# A_D_000000_001.net
KiCad netlist of a schematic drawn in Altium Designer
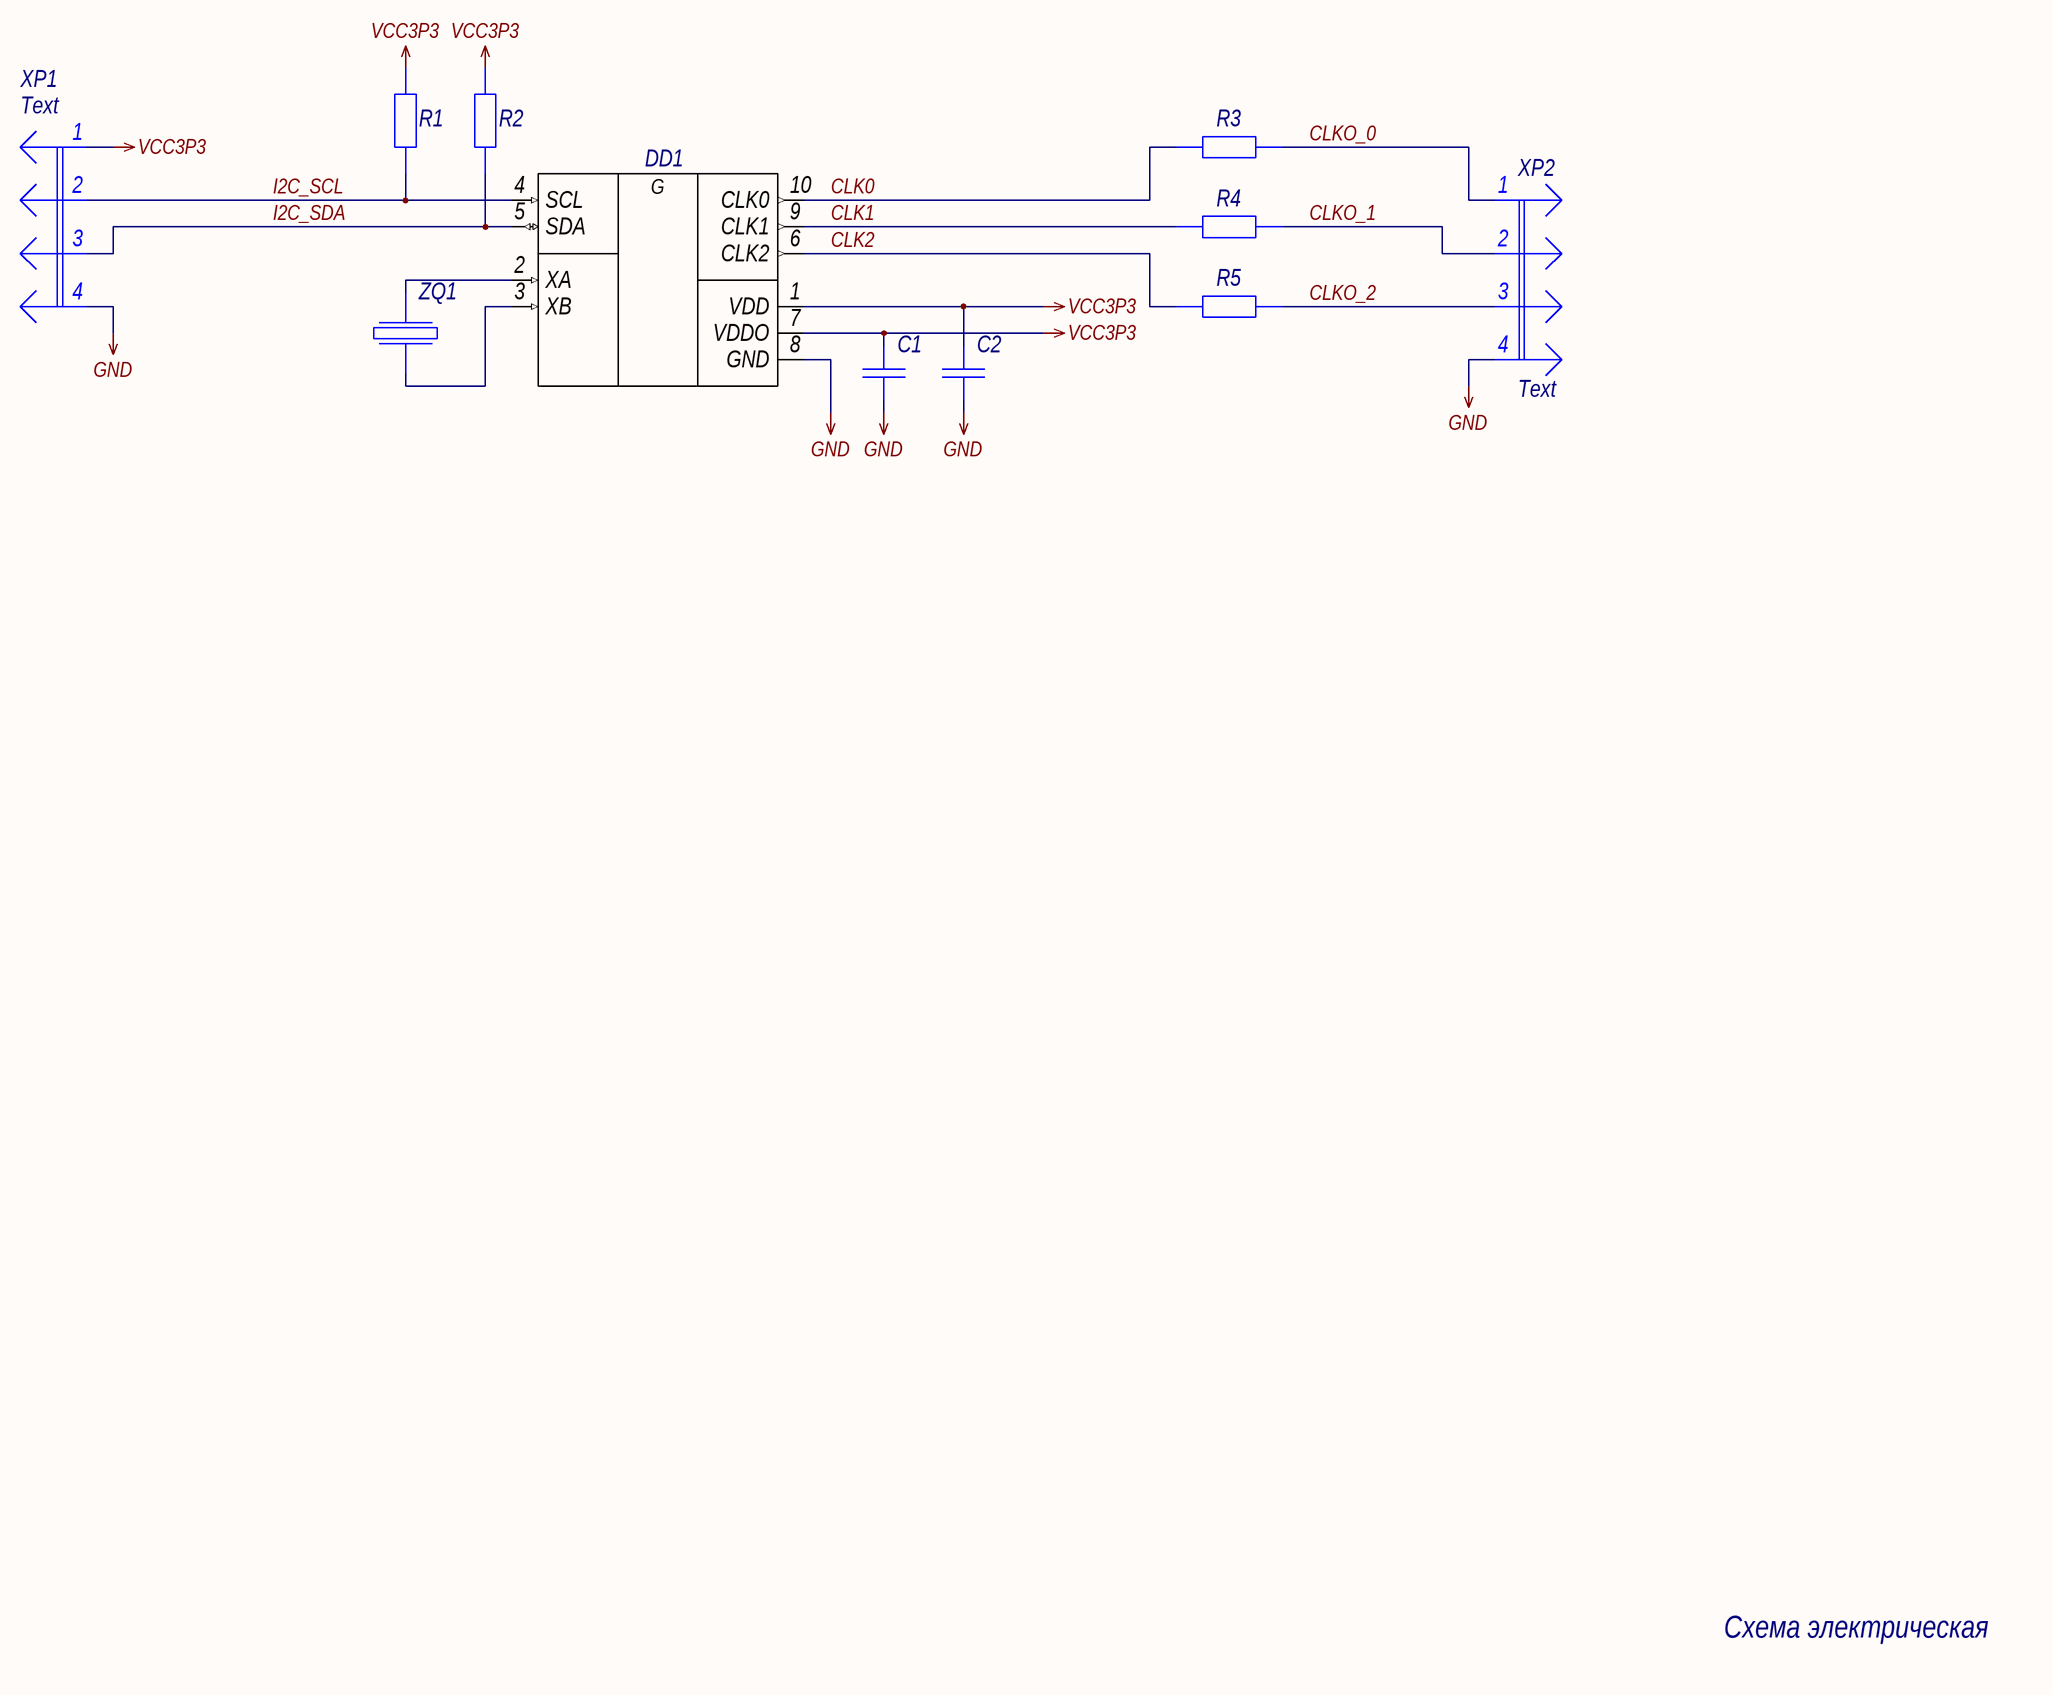
[diagram p0: A_D.000000.001.SchDoc]

(export (version "E")
  (design (tool "Eeschema 10.0.6"))
  (components
    (comp (ref "C1")
      (value "Capacitor")
      (footprint "C0603_L")
      (fields
        (field (name "PART NUMBER") "GRM188R61C225KE15D")
        (field (name "VOLTAGE") "16V")
        (field (name "TOLERANCE") "±10%")
        (field (name "PUBLISHER") "Andrew Danich")
      )
      (libsource (lib "Lib_IMP_GOST") (part "Capacitor"))
    )
    (comp (ref "C2")
      (value "Capacitor")
      (footprint "C0603_L")
      (fields
        (field (name "PART NUMBER") "GRM188R71E104KA01D")
        (field (name "VOLTAGE") "25V")
        (field (name "TOLERANCE") "±10%")
        (field (name "PUBLISHER") "Andrew Danich")
      )
      (libsource (lib "Lib_IMP_GOST") (part "Capacitor"))
    )
    (comp (ref "DD1")
      (value "Si5351x-x-GT")
      (footprint "MSOP-10")
      (fields
        (field (name "PART NUMBER") "Si5351A-B-GT")
        (field (name "MANUFACTURER") "Silicon Labs")
        (field (name "PUBLISHER") "Andrew Danich")
      )
      (libsource (lib "Lib_IMP_GOST") (part "Si5351x-x-GT"))
    )
    (comp (ref "R1")
      (value "Resistor")
      (footprint "R0603_L")
      (fields
        (field (name "PART NUMBER") "RC0603JR-074K7L")
        (field (name "TOLERANCE") "±5%")
        (field (name "MANUFACTURER") "Yageo")
        (field (name "PUBLISHER") "Andrew Danich")
      )
      (libsource (lib "Lib_IMP_GOST") (part "Resistor"))
    )
    (comp (ref "R2")
      (value "Resistor")
      (footprint "R0603_L")
      (fields
        (field (name "PART NUMBER") "RC0603JR-074K7L")
        (field (name "TOLERANCE") "±5%")
        (field (name "MANUFACTURER") "Yageo")
        (field (name "PUBLISHER") "Andrew Danich")
      )
      (libsource (lib "Lib_IMP_GOST") (part "Resistor"))
    )
    (comp (ref "R3")
      (value "Resistor")
      (footprint "R0603_L")
      (fields
        (field (name "PART NUMBER") "RC0603JR-070R")
        (field (name "TOLERANCE") "±5%")
        (field (name "MANUFACTURER") "Yageo")
        (field (name "PUBLISHER") "Andrew Danich")
      )
      (libsource (lib "Lib_IMP_GOST") (part "Resistor"))
    )
    (comp (ref "R4")
      (value "Resistor")
      (footprint "R0603_L")
      (fields
        (field (name "PART NUMBER") "RC0603JR-070R")
        (field (name "TOLERANCE") "±5%")
        (field (name "MANUFACTURER") "Yageo")
        (field (name "PUBLISHER") "Andrew Danich")
      )
      (libsource (lib "Lib_IMP_GOST") (part "Resistor"))
    )
    (comp (ref "R5")
      (value "Resistor")
      (footprint "R0603_L")
      (fields
        (field (name "PART NUMBER") "RC0603JR-070R")
        (field (name "TOLERANCE") "±5%")
        (field (name "MANUFACTURER") "Yageo")
        (field (name "PUBLISHER") "Andrew Danich")
      )
      (libsource (lib "Lib_IMP_GOST") (part "Resistor"))
    )
    (comp (ref "XP1")
      (value "Text")
      (footprint "PLS-4")
      (fields (field (name "PART NUMBER") "PLS-4") (field (name "PUBLISHER") "Andrew Danich"))
      (libsource (lib "Lib_IMP_GOST") (part "Con-4-M"))
    )
    (comp (ref "XP2")
      (value "Text")
      (footprint "PLS-4")
      (fields (field (name "PART NUMBER") "PLS-4") (field (name "PUBLISHER") "Andrew Danich"))
      (libsource (lib "Lib_IMP_GOST") (part "Con-4-M"))
    )
    (comp (ref "ZQ1")
      (value "Crystal-1_3p")
      (footprint "SMD 3.2x2.5mm")
      (fields
        (field (name "PART NUMBER") "12.88667_KX-7-25.0MHz")
        (field (name "MANUFACTURER") "GEYER ELECTRONIC")
        (field (name "PUBLISHER") "Andrew Danich")
      )
      (libsource (lib "Lib_IMP_GOST") (part "Crystal-1_3p"))
    )
  )
  (nets
    (net (code "1") (name "/CLK0") (class "Default")
      (node (ref "DD1") (pin "10") (pinfunction "CLK0_10") (pintype "output"))
      (node (ref "R3") (pin "1") (pinfunction "1_1") (pintype "passive"))
    )
    (net (code "2") (name "/CLK1") (class "Default")
      (node (ref "DD1") (pin "9") (pinfunction "CLK1_9") (pintype "output"))
      (node (ref "R4") (pin "1") (pinfunction "1_1") (pintype "passive"))
    )
    (net (code "3") (name "/CLK2") (class "Default")
      (node (ref "DD1") (pin "6") (pinfunction "CLK2_6") (pintype "output"))
      (node (ref "R5") (pin "1") (pinfunction "1_1") (pintype "passive"))
    )
    (net (code "4") (name "/CLKO_0") (class "Default")
      (node (ref "R3") (pin "2") (pinfunction "2_2") (pintype "passive"))
      (node (ref "XP2") (pin "1") (pintype "passive"))
    )
    (net (code "5") (name "/CLKO_1") (class "Default")
      (node (ref "R4") (pin "2") (pinfunction "2_2") (pintype "passive"))
      (node (ref "XP2") (pin "2") (pintype "passive"))
    )
    (net (code "6") (name "/CLKO_2") (class "Default")
      (node (ref "R5") (pin "2") (pinfunction "2_2") (pintype "passive"))
      (node (ref "XP2") (pin "3") (pintype "passive"))
    )
    (net (code "7") (name "/I2C_SCL") (class "Default")
      (node (ref "DD1") (pin "4") (pinfunction "SCL_4") (pintype "input"))
      (node (ref "R1") (pin "1") (pinfunction "1_1") (pintype "passive"))
      (node (ref "XP1") (pin "2") (pintype "passive"))
    )
    (net (code "8") (name "/I2C_SDA") (class "Default")
      (node (ref "DD1") (pin "5") (pinfunction "SDA_5") (pintype "bidirectional"))
      (node (ref "R2") (pin "1") (pinfunction "1_1") (pintype "passive"))
      (node (ref "XP1") (pin "3") (pintype "passive"))
    )
    (net (code "9") (name "GND") (class "Default")
      (node (ref "C1") (pin "1") (pinfunction "1_1") (pintype "passive"))
      (node (ref "C2") (pin "1") (pinfunction "1_1") (pintype "passive"))
      (node (ref "DD1") (pin "8") (pinfunction "GND_8") (pintype "power_in"))
      (node (ref "XP1") (pin "4") (pintype "passive"))
      (node (ref "XP2") (pin "4") (pintype "passive"))
    )
    (net (code "10") (name "Net-(DD1-XA)") (class "Default")
      (node (ref "DD1") (pin "2") (pinfunction "XA_2") (pintype "input"))
      (node (ref "ZQ1") (pin "1") (pinfunction "1_1") (pintype "passive"))
    )
    (net (code "11") (name "Net-(DD1-XB)") (class "Default")
      (node (ref "DD1") (pin "3") (pinfunction "XB_3") (pintype "input"))
      (node (ref "ZQ1") (pin "3") (pinfunction "3_3") (pintype "passive"))
    )
    (net (code "12") (name "VCC3P3") (class "Default")
      (node (ref "C1") (pin "2") (pinfunction "2_2") (pintype "passive"))
      (node (ref "C2") (pin "2") (pinfunction "2_2") (pintype "passive"))
      (node (ref "DD1") (pin "1") (pinfunction "VDD_1") (pintype "power_in"))
      (node (ref "DD1") (pin "7") (pinfunction "VDDO_7") (pintype "power_in"))
      (node (ref "R1") (pin "2") (pinfunction "2_2") (pintype "passive"))
      (node (ref "R2") (pin "2") (pinfunction "2_2") (pintype "passive"))
      (node (ref "XP1") (pin "1") (pintype "passive"))
    )
  )
)
